# TDA2003-Amplifier-Stereo.net
KiCad netlist of a schematic drawn in EAGLE
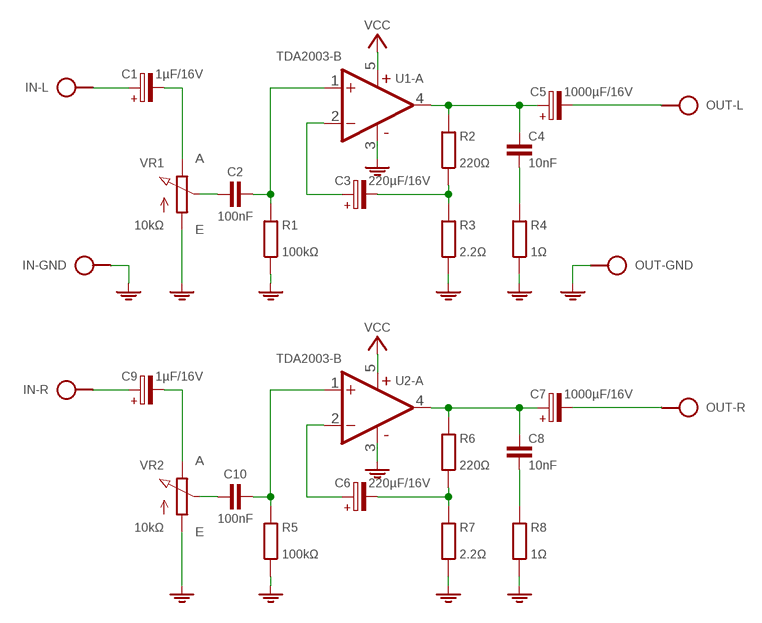
[diagram p0: schematic, sheet 1]

(export (version "E")
  (design (tool "Eeschema 10.0.6"))
  (components
    (comp (ref "C1")
      (value "1µF/16V")
      (footprint "eagle-import:E2,5-4")
      (libsource (lib "eagle-import") (part "CPOL-HE2,5-4"))
    )
    (comp (ref "C2")
      (value "100nF")
      (footprint "eagle-import:C050-020X044_V")
      (libsource (lib "eagle-import") (part "C-H050-020X044/V"))
    )
    (comp (ref "C3")
      (value "220µF/16V")
      (footprint "eagle-import:E5-5")
      (libsource (lib "eagle-import") (part "CPOL-HE5-5"))
    )
    (comp (ref "C4")
      (value "10nF")
      (footprint "eagle-import:C050-025X075_V")
      (libsource (lib "eagle-import") (part "C050-025X075/V"))
    )
    (comp (ref "C5")
      (value "1000µF/16V")
      (footprint "eagle-import:E5-5")
      (libsource (lib "eagle-import") (part "CPOL-HE5-5"))
    )
    (comp (ref "C6")
      (value "220µF/16V")
      (footprint "eagle-import:E5-5")
      (libsource (lib "eagle-import") (part "CPOL-HE5-5"))
    )
    (comp (ref "C7")
      (value "1000µF/16V")
      (footprint "eagle-import:E5-5")
      (libsource (lib "eagle-import") (part "CPOL-HE5-5"))
    )
    (comp (ref "C8")
      (value "10nF")
      (footprint "eagle-import:C050-025X075_V")
      (libsource (lib "eagle-import") (part "C050-025X075/V"))
    )
    (comp (ref "C9")
      (value "1µF/16V")
      (footprint "eagle-import:E2,5-4")
      (libsource (lib "eagle-import") (part "CPOL-HE2,5-4"))
    )
    (comp (ref "C10")
      (value "100nF")
      (footprint "eagle-import:C050-020X044_V")
      (libsource (lib "eagle-import") (part "C-H050-020X044/V"))
    )
    (comp (ref "IN")
      (value "SAUDIO")
      (footprint "eagle-import:SPAD-3")
      (libsource (lib "eagle-import") (part "SAUDIO"))
    )
    (comp (ref "OUT")
      (value "SAUDIO")
      (footprint "eagle-import:SPAD-3")
      (libsource (lib "eagle-import") (part "SAUDIO"))
    )
    (comp (ref "PWR")
      (value "VCC_GNDL")
      (footprint "eagle-import:SPAD-+")
      (libsource (lib "eagle-import") (part "VCC_GNDL"))
    )
    (comp (ref "PWR1")
      (value "VCC_GNDL")
      (footprint "eagle-import:SPAD-+")
      (libsource (lib "eagle-import") (part "VCC_GNDL"))
    )
    (comp (ref "R1")
      (value "100kΩ")
      (footprint "eagle-import:0204_10-V")
      (libsource (lib "eagle-import") (part "R0204/10-V"))
    )
    (comp (ref "R2")
      (value "220Ω")
      (footprint "eagle-import:0204_10-V")
      (libsource (lib "eagle-import") (part "R0204/10-V"))
    )
    (comp (ref "R3")
      (value "2.2Ω")
      (footprint "eagle-import:0204_10-V")
      (libsource (lib "eagle-import") (part "R0204/10-V"))
    )
    (comp (ref "R4")
      (value "1Ω")
      (footprint "eagle-import:0204_10-V")
      (libsource (lib "eagle-import") (part "R0204/10-V"))
    )
    (comp (ref "R5")
      (value "100kΩ")
      (footprint "eagle-import:0204_10-V")
      (libsource (lib "eagle-import") (part "R0204/10-V"))
    )
    (comp (ref "R6")
      (value "220Ω")
      (footprint "eagle-import:0204_10-V")
      (libsource (lib "eagle-import") (part "R0204/10-V"))
    )
    (comp (ref "R7")
      (value "2.2Ω")
      (footprint "eagle-import:0204_10-V")
      (libsource (lib "eagle-import") (part "R0204/10-V"))
    )
    (comp (ref "R8")
      (value "1Ω")
      (footprint "eagle-import:0204_10-V")
      (libsource (lib "eagle-import") (part "R0204/10-V"))
    )
    (comp (ref "U1")
      (value "TDA2003-B")
      (footprint "eagle-import:TO220-B5")
      (libsource (lib "eagle-import") (part "TDA2003-B"))
    )
    (comp (ref "U2")
      (value "TDA2003-B")
      (footprint "eagle-import:TO220-B5")
      (libsource (lib "eagle-import") (part "TDA2003-B"))
    )
    (comp (ref "VR1")
      (value "10kΩ")
      (footprint "eagle-import:CONN-3P")
      (libsource (lib "eagle-import") (part "POT-3P"))
    )
    (comp (ref "VR2")
      (value "10kΩ")
      (footprint "eagle-import:CONN-3P")
      (libsource (lib "eagle-import") (part "POT-3P"))
    )
  )
  (nets
    (net (code "1") (name "/VCC") (class "Default")
      (node (ref "PWR") (pin "2") (pinfunction "VCC_2") (pintype "power_in"))
      (node (ref "PWR1") (pin "2") (pinfunction "VCC_2") (pintype "power_in"))
      (node (ref "U1") (pin "5") (pinfunction "V+_5") (pintype "power_in"))
      (node (ref "U2") (pin "5") (pinfunction "V+_5") (pintype "power_in"))
    )
    (net (code "2") (name "GND") (class "Default")
      (node (ref "IN") (pin "2") (pinfunction "P$1_2") (pintype "passive"))
      (node (ref "OUT") (pin "2") (pinfunction "P$1_2") (pintype "passive"))
      (node (ref "PWR") (pin "1") (pinfunction "GND_1") (pintype "power_in"))
      (node (ref "PWR1") (pin "1") (pinfunction "GND_1") (pintype "power_in"))
      (node (ref "R1") (pin "2") (pinfunction "1_2") (pintype "passive"))
      (node (ref "R3") (pin "2") (pinfunction "1_2") (pintype "passive"))
      (node (ref "R4") (pin "2") (pinfunction "1_2") (pintype "passive"))
      (node (ref "R5") (pin "2") (pinfunction "1_2") (pintype "passive"))
      (node (ref "R7") (pin "2") (pinfunction "1_2") (pintype "passive"))
      (node (ref "R8") (pin "2") (pinfunction "1_2") (pintype "passive"))
      (node (ref "U1") (pin "3") (pinfunction "V-_3") (pintype "power_in"))
      (node (ref "U2") (pin "3") (pinfunction "V-_3") (pintype "power_in"))
      (node (ref "VR1") (pin "1") (pinfunction "A_1") (pintype "passive"))
      (node (ref "VR2") (pin "1") (pinfunction "A_1") (pintype "passive"))
    )
    (net (code "3") (name "Net-(INB-P$1)") (class "Default")
      (node (ref "C1") (pin "+") (pinfunction "+_+") (pintype "passive"))
      (node (ref "IN") (pin "1") (pinfunction "P$1_1") (pintype "passive"))
    )
    (net (code "4") (name "Net-(INC-P$1)") (class "Default")
      (node (ref "C9") (pin "+") (pinfunction "+_+") (pintype "passive"))
      (node (ref "IN") (pin "3") (pinfunction "P$1_3") (pintype "passive"))
    )
    (net (code "5") (name "Net-(OUTB-P$1)") (class "Default")
      (node (ref "C5") (pin "-") (pinfunction "-_-") (pintype "passive"))
      (node (ref "OUT") (pin "1") (pinfunction "P$1_1") (pintype "passive"))
    )
    (net (code "6") (name "Net-(OUTC-P$1)") (class "Default")
      (node (ref "C7") (pin "-") (pinfunction "-_-") (pintype "passive"))
      (node (ref "OUT") (pin "3") (pinfunction "P$1_3") (pintype "passive"))
    )
    (net (code "7") (name "Net-(R1-2)") (class "Default")
      (node (ref "C2") (pin "2") (pinfunction "2_2") (pintype "passive"))
      (node (ref "R1") (pin "1") (pinfunction "2_1") (pintype "passive"))
      (node (ref "U1") (pin "1") (pinfunction "+IN_1") (pintype "input"))
    )
    (net (code "8") (name "Net-(R2-1)") (class "Default")
      (node (ref "C3") (pin "-") (pinfunction "-_-") (pintype "passive"))
      (node (ref "R2") (pin "2") (pinfunction "1_2") (pintype "passive"))
      (node (ref "R3") (pin "1") (pinfunction "2_1") (pintype "passive"))
    )
    (net (code "9") (name "Net-(R2-2)") (class "Default")
      (node (ref "C4") (pin "1") (pinfunction "1_1") (pintype "passive"))
      (node (ref "C5") (pin "+") (pinfunction "+_+") (pintype "passive"))
      (node (ref "R2") (pin "1") (pinfunction "2_1") (pintype "passive"))
      (node (ref "U1") (pin "4") (pinfunction "OUT_4") (pintype "output"))
    )
    (net (code "10") (name "Net-(R4-2)") (class "Default")
      (node (ref "C4") (pin "2") (pinfunction "2_2") (pintype "passive"))
      (node (ref "R4") (pin "1") (pinfunction "2_1") (pintype "passive"))
    )
    (net (code "11") (name "Net-(R5-2)") (class "Default")
      (node (ref "C10") (pin "2") (pinfunction "2_2") (pintype "passive"))
      (node (ref "R5") (pin "1") (pinfunction "2_1") (pintype "passive"))
      (node (ref "U2") (pin "1") (pinfunction "+IN_1") (pintype "input"))
    )
    (net (code "12") (name "Net-(R6-1)") (class "Default")
      (node (ref "C6") (pin "-") (pinfunction "-_-") (pintype "passive"))
      (node (ref "R6") (pin "2") (pinfunction "1_2") (pintype "passive"))
      (node (ref "R7") (pin "1") (pinfunction "2_1") (pintype "passive"))
    )
    (net (code "13") (name "Net-(R6-2)") (class "Default")
      (node (ref "C7") (pin "+") (pinfunction "+_+") (pintype "passive"))
      (node (ref "C8") (pin "1") (pinfunction "1_1") (pintype "passive"))
      (node (ref "R6") (pin "1") (pinfunction "2_1") (pintype "passive"))
      (node (ref "U2") (pin "4") (pinfunction "OUT_4") (pintype "output"))
    )
    (net (code "14") (name "Net-(R8-2)") (class "Default")
      (node (ref "C8") (pin "2") (pinfunction "2_2") (pintype "passive"))
      (node (ref "R8") (pin "1") (pinfunction "2_1") (pintype "passive"))
    )
    (net (code "15") (name "Net-(U1A--IN)") (class "Default")
      (node (ref "C3") (pin "+") (pinfunction "+_+") (pintype "passive"))
      (node (ref "U1") (pin "2") (pinfunction "-IN_2") (pintype "input"))
    )
    (net (code "16") (name "Net-(U2A--IN)") (class "Default")
      (node (ref "C6") (pin "+") (pinfunction "+_+") (pintype "passive"))
      (node (ref "U2") (pin "2") (pinfunction "-IN_2") (pintype "input"))
    )
    (net (code "17") (name "Net-(VR1-E)") (class "Default")
      (node (ref "C1") (pin "-") (pinfunction "-_-") (pintype "passive"))
      (node (ref "VR1") (pin "3") (pinfunction "E_3") (pintype "passive"))
    )
    (net (code "18") (name "Net-(VR1-S)") (class "Default")
      (node (ref "C2") (pin "1") (pinfunction "1_1") (pintype "passive"))
      (node (ref "VR1") (pin "2") (pinfunction "S_2") (pintype "passive"))
    )
    (net (code "19") (name "Net-(VR2-E)") (class "Default")
      (node (ref "C9") (pin "-") (pinfunction "-_-") (pintype "passive"))
      (node (ref "VR2") (pin "3") (pinfunction "E_3") (pintype "passive"))
    )
    (net (code "20") (name "Net-(VR2-S)") (class "Default")
      (node (ref "C10") (pin "1") (pinfunction "1_1") (pintype "passive"))
      (node (ref "VR2") (pin "2") (pinfunction "S_2") (pintype "passive"))
    )
  )
)
